# minimalist_receiver_circuit.net
KiCad netlist of a schematic drawn in EAGLE
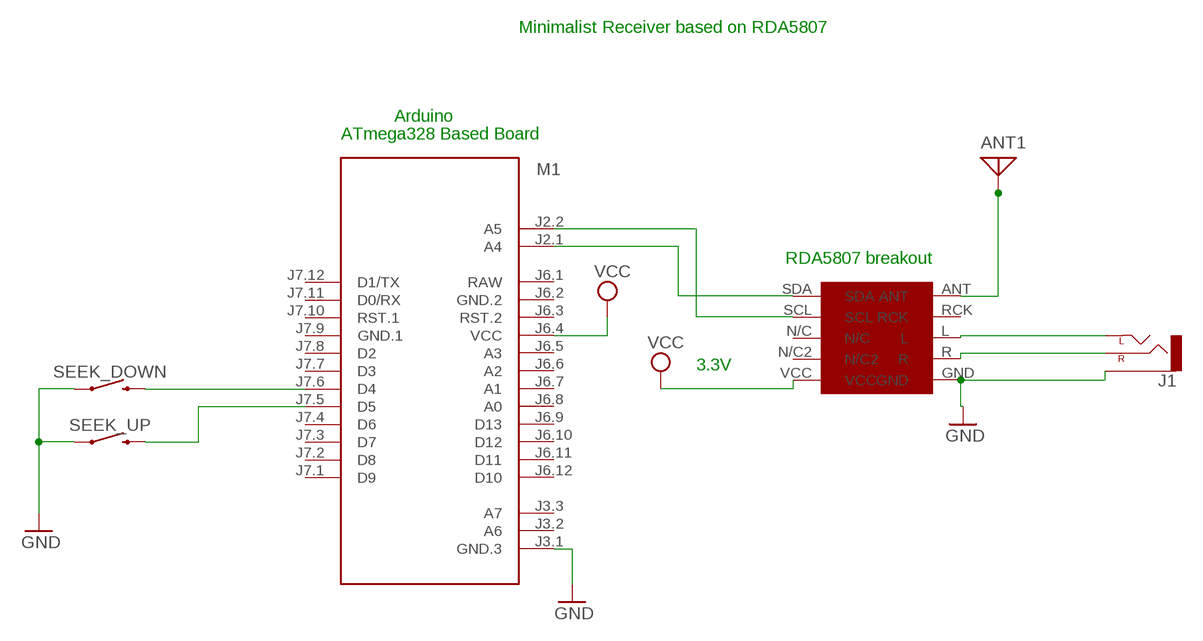
[diagram p0: schematic, sheet 1]

(export (version "E")
  (design (tool "Eeschema 10.0.6"))
  (components
    (comp (ref "ANT1")
      (value "ANTENNA")
      (footprint "eagle-import:PAD-01")
      (libsource (lib "eagle-import") (part "ANTENNA"))
    )
    (comp (ref "J1")
      (value "AUDIO_JACK_2.5MMSPECIAL_POGO_PINS")
      (footprint "eagle-import:STEREOJACK2.5MM_SPECIAL_POGOPINS")
      (libsource (lib "eagle-import") (part "AUDIO_JACK_2.5MMSPECIAL_POGO_PINS"))
    )
    (comp (ref "M1")
      (value "ARDUINO-PRO-MINI-3.3V#APC")
      (footprint "eagle-import:ARDUINO-PRO-MINI#APC")
      (libsource (lib "eagle-import") (part "ARDUINO-PRO-MINI-#APC3.3V"))
    )
    (comp (ref "SEEK_DOWN")
      (value "MOMENTARY-SWITCH-SPST-PTH-6.0MM")
      (footprint "eagle-import:TACTILE_SWITCH_PTH_6.0MM")
      (libsource (lib "eagle-import") (part "MOMENTARY-SWITCH-SPST-PTH-6.0MM"))
    )
    (comp (ref "SEEK_UP")
      (value "MOMENTARY-SWITCH-SPST-PTH-6.0MM")
      (footprint "eagle-import:TACTILE_SWITCH_PTH_6.0MM")
      (libsource (lib "eagle-import") (part "MOMENTARY-SWITCH-SPST-PTH-6.0MM"))
    )
    (comp (ref "U$1")
      (value "RDA")
      (footprint "eagle-import:RDA")
      (libsource (lib "eagle-import") (part "RDA"))
    )
  )
  (nets
    (net (code "1") (name "/GND.1") (class "Default")
      (node (ref "M1") (pin "J7.9") (pinfunction "GND.1_J7.9") (pintype "power_in"))
    )
    (net (code "2") (name "/GND.2") (class "Default")
      (node (ref "M1") (pin "J6.2") (pinfunction "GND.2_J6.2") (pintype "power_in"))
    )
    (net (code "3") (name "/RAW") (class "Default")
      (node (ref "M1") (pin "J6.1") (pinfunction "RAW_J6.1") (pintype "power_in"))
    )
    (net (code "4") (name "GND") (class "Default")
      (node (ref "J1") (pin "RING1") (pinfunction "SLEEVE_RING1") (pintype "bidirectional"))
      (node (ref "M1") (pin "J3.1") (pinfunction "GND.3_J3.1") (pintype "bidirectional"))
      (node (ref "SEEK_DOWN") (pin "1") (pinfunction "1_1") (pintype "passive"))
      (node (ref "SEEK_UP") (pin "1") (pinfunction "1_1") (pintype "passive"))
      (node (ref "U$1") (pin "GND") (pinfunction "GND_GND") (pintype "power_in"))
    )
    (net (code "5") (name "Net-(ANT1-Pad1)") (class "Default")
      (node (ref "ANT1") (pin "1") (pinfunction "1_1") (pintype "output"))
      (node (ref "U$1") (pin "ANT") (pinfunction "ANT_ANT") (pintype "input"))
    )
    (net (code "6") (name "Net-(J1-LEFT)") (class "Default")
      (node (ref "J1") (pin "SHIELD") (pinfunction "LEFT_SHIELD") (pintype "bidirectional"))
      (node (ref "U$1") (pin "L") (pinfunction "L_L") (pintype "output"))
    )
    (net (code "7") (name "Net-(J1-RIGHT)") (class "Default")
      (node (ref "J1") (pin "TIP") (pinfunction "RIGHT_TIP") (pintype "bidirectional"))
      (node (ref "U$1") (pin "R") (pinfunction "R_R") (pintype "output"))
    )
    (net (code "8") (name "Net-(M1-A4)") (class "Default")
      (node (ref "M1") (pin "J2.1") (pinfunction "A4_J2.1") (pintype "bidirectional"))
      (node (ref "U$1") (pin "SDA") (pinfunction "SDA_SDA") (pintype "bidirectional"))
    )
    (net (code "9") (name "Net-(M1-A5)") (class "Default")
      (node (ref "M1") (pin "J2.2") (pinfunction "A5_J2.2") (pintype "bidirectional"))
      (node (ref "U$1") (pin "SCL") (pinfunction "SCL_SCL") (pintype "bidirectional"))
    )
    (net (code "10") (name "Net-(M1-D4)") (class "Default")
      (node (ref "M1") (pin "J7.6") (pinfunction "D4_J7.6") (pintype "bidirectional"))
      (node (ref "SEEK_DOWN") (pin "3") (pinfunction "2_3") (pintype "passive"))
    )
    (net (code "11") (name "Net-(M1-D5)") (class "Default")
      (node (ref "M1") (pin "J7.5") (pinfunction "D5_J7.5") (pintype "bidirectional"))
      (node (ref "SEEK_UP") (pin "3") (pinfunction "2_3") (pintype "passive"))
    )
    (net (code "12") (name "VCC") (class "Default")
      (node (ref "M1") (pin "J6.4") (pinfunction "VCC_J6.4") (pintype "power_in"))
      (node (ref "U$1") (pin "VCC") (pinfunction "VCC_VCC") (pintype "power_in"))
    )
    (net (code "13") (name "unconnected-(M1-A0-PadJ6.8)") (class "Default")
      (node (ref "M1") (pin "J6.8") (pinfunction "A0_J6.8") (pintype "bidirectional"))
    )
    (net (code "14") (name "unconnected-(M1-A1-PadJ6.7)") (class "Default")
      (node (ref "M1") (pin "J6.7") (pinfunction "A1_J6.7") (pintype "bidirectional"))
    )
    (net (code "15") (name "unconnected-(M1-A2-PadJ6.6)") (class "Default")
      (node (ref "M1") (pin "J6.6") (pinfunction "A2_J6.6") (pintype "bidirectional"))
    )
    (net (code "16") (name "unconnected-(M1-A3-PadJ6.5)") (class "Default")
      (node (ref "M1") (pin "J6.5") (pinfunction "A3_J6.5") (pintype "bidirectional"))
    )
    (net (code "17") (name "unconnected-(M1-A6-PadJ3.2)") (class "Default")
      (node (ref "M1") (pin "J3.2") (pinfunction "A6_J3.2") (pintype "bidirectional"))
    )
    (net (code "18") (name "unconnected-(M1-A7-PadJ3.3)") (class "Default")
      (node (ref "M1") (pin "J3.3") (pinfunction "A7_J3.3") (pintype "bidirectional"))
    )
    (net (code "19") (name "unconnected-(M1-D0{slash}RX-PadJ7.11)") (class "Default")
      (node (ref "M1") (pin "J7.11") (pinfunction "D0/RX_J7.11") (pintype "bidirectional"))
    )
    (net (code "20") (name "unconnected-(M1-D1{slash}TX-PadJ7.12)") (class "Default")
      (node (ref "M1") (pin "J7.12") (pinfunction "D1/TX_J7.12") (pintype "bidirectional"))
    )
    (net (code "21") (name "unconnected-(M1-D2-PadJ7.8)") (class "Default")
      (node (ref "M1") (pin "J7.8") (pinfunction "D2_J7.8") (pintype "bidirectional"))
    )
    (net (code "22") (name "unconnected-(M1-D3-PadJ7.7)") (class "Default")
      (node (ref "M1") (pin "J7.7") (pinfunction "D3_J7.7") (pintype "bidirectional"))
    )
    (net (code "23") (name "unconnected-(M1-D6-PadJ7.4)") (class "Default")
      (node (ref "M1") (pin "J7.4") (pinfunction "D6_J7.4") (pintype "bidirectional"))
    )
    (net (code "24") (name "unconnected-(M1-D7-PadJ7.3)") (class "Default")
      (node (ref "M1") (pin "J7.3") (pinfunction "D7_J7.3") (pintype "bidirectional"))
    )
    (net (code "25") (name "unconnected-(M1-D8-PadJ7.2)") (class "Default")
      (node (ref "M1") (pin "J7.2") (pinfunction "D8_J7.2") (pintype "bidirectional"))
    )
    (net (code "26") (name "unconnected-(M1-D9-PadJ7.1)") (class "Default")
      (node (ref "M1") (pin "J7.1") (pinfunction "D9_J7.1") (pintype "bidirectional"))
    )
    (net (code "27") (name "unconnected-(M1-D10-PadJ6.12)") (class "Default")
      (node (ref "M1") (pin "J6.12") (pinfunction "D10_J6.12") (pintype "bidirectional"))
    )
    (net (code "28") (name "unconnected-(M1-D11-PadJ6.11)") (class "Default")
      (node (ref "M1") (pin "J6.11") (pinfunction "D11_J6.11") (pintype "bidirectional"))
    )
    (net (code "29") (name "unconnected-(M1-D12-PadJ6.10)") (class "Default")
      (node (ref "M1") (pin "J6.10") (pinfunction "D12_J6.10") (pintype "bidirectional"))
    )
    (net (code "30") (name "unconnected-(M1-D13-PadJ6.9)") (class "Default")
      (node (ref "M1") (pin "J6.9") (pinfunction "D13_J6.9") (pintype "bidirectional"))
    )
    (net (code "31") (name "unconnected-(M1-RST.1-PadJ7.10)") (class "Default")
      (node (ref "M1") (pin "J7.10") (pinfunction "RST.1_J7.10") (pintype "bidirectional"))
    )
    (net (code "32") (name "unconnected-(M1-RST.2-PadJ6.3)") (class "Default")
      (node (ref "M1") (pin "J6.3") (pinfunction "RST.2_J6.3") (pintype "bidirectional"))
    )
    (net (code "33") (name "unconnected-(U$1-PadN{slash}C)") (class "Default")
      (node (ref "U$1") (pin "N/C") (pinfunction "N/C_N/C") (pintype "passive"))
    )
    (net (code "34") (name "unconnected-(U$1-PadN{slash}C2)") (class "Default")
      (node (ref "U$1") (pin "N/C2") (pinfunction "N/C2_N/C2") (pintype "passive"))
    )
    (net (code "35") (name "unconnected-(U$1-PadRCK)") (class "Default")
      (node (ref "U$1") (pin "RCK") (pinfunction "RCK_RCK") (pintype "bidirectional"))
    )
  )
)
